# M_B_adapter_412.net
KiCad netlist of a schematic drawn in EAGLE
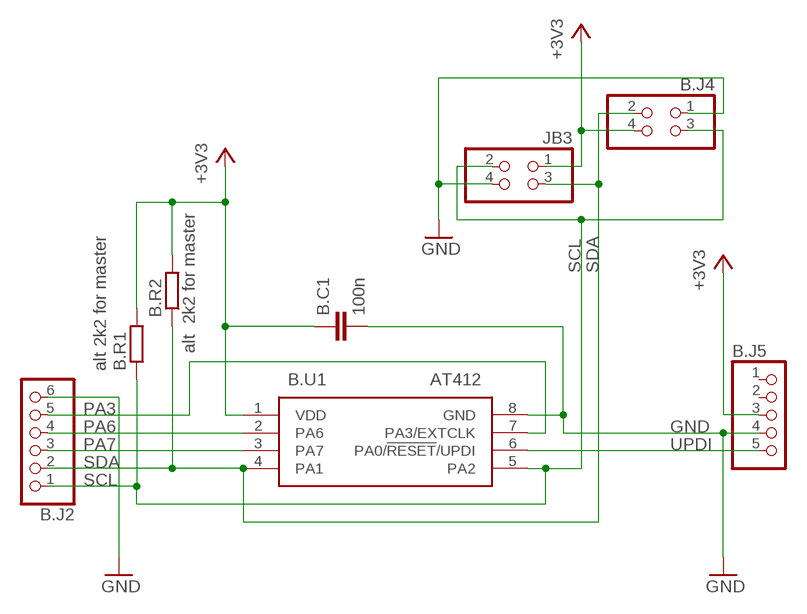
[diagram p0: schematic, sheet 1]

(export (version "E")
  (design (tool "Eeschema 10.0.6"))
  (components
    (comp (ref "B.C1")
      (value "100n")
      (footprint "eagle-import:C0603")
      (libsource (lib "eagle-import") (part "C-EUC0603"))
    )
    (comp (ref "B.J2")
      (value "PINHD-1X6")
      (footprint "eagle-import:1X06")
      (libsource (lib "eagle-import") (part "PINHD-1X6"))
    )
    (comp (ref "B.J4")
      (value "PINHD-2X2")
      (footprint "eagle-import:2X02")
      (libsource (lib "eagle-import") (part "PINHD-2X2"))
    )
    (comp (ref "B.J5")
      (value "PINHD-1X5")
      (footprint "eagle-import:1X05")
      (libsource (lib "eagle-import") (part "PINHD-1X5"))
    )
    (comp (ref "B.R1")
      (value "alt 2k2 for master")
      (footprint "eagle-import:R0603")
      (libsource (lib "eagle-import") (part "R-EU_R0603"))
    )
    (comp (ref "B.R2")
      (value "alt 2k2 for master")
      (footprint "eagle-import:R0603")
      (libsource (lib "eagle-import") (part "R-EU_R0603"))
    )
    (comp (ref "B.U1")
      (value "AT412")
      (footprint "eagle-import:SOIC127P600X175-8N")
      (fields
        (field (name "MANUFACTURER_PART_NUMBER") "ATTINY412-SSN")
        (field (name "MOUSER_PART_NUMBER") "579-ATTINY412-SSN")
      )
      (libsource (lib "eagle-import") (part "ATTINY412-SSN"))
    )
    (comp (ref "JB3")
      (value "PINHD-2X2")
      (footprint "eagle-import:2X02")
      (libsource (lib "eagle-import") (part "PINHD-2X2"))
    )
  )
  (nets
    (net (code "1") (name "+3V3") (class "Default")
      (node (ref "B.C1") (pin "1") (pinfunction "1_1") (pintype "passive"))
      (node (ref "B.J4") (pin "4") (pinfunction "4_4") (pintype "passive"))
      (node (ref "B.J5") (pin "3") (pinfunction "3_3") (pintype "passive"))
      (node (ref "B.R1") (pin "2") (pinfunction "2_2") (pintype "passive"))
      (node (ref "B.R2") (pin "2") (pinfunction "2_2") (pintype "passive"))
      (node (ref "B.U1") (pin "1") (pinfunction "VDD_1") (pintype "bidirectional"))
      (node (ref "JB3") (pin "1") (pinfunction "1_1") (pintype "passive"))
    )
    (net (code "2") (name "/PA3") (class "Default")
      (node (ref "B.J2") (pin "5") (pinfunction "5_5") (pintype "passive"))
      (node (ref "B.U1") (pin "7") (pinfunction "PA3/EXTCLK_7") (pintype "bidirectional"))
    )
    (net (code "3") (name "/PA6") (class "Default")
      (node (ref "B.J2") (pin "4") (pinfunction "4_4") (pintype "passive"))
      (node (ref "B.U1") (pin "2") (pinfunction "PA6_2") (pintype "bidirectional"))
    )
    (net (code "4") (name "/PA7") (class "Default")
      (node (ref "B.J2") (pin "3") (pinfunction "3_3") (pintype "passive"))
      (node (ref "B.U1") (pin "3") (pinfunction "PA7_3") (pintype "bidirectional"))
    )
    (net (code "5") (name "/SCL") (class "Default")
      (node (ref "B.J2") (pin "1") (pinfunction "1_1") (pintype "passive"))
      (node (ref "B.J4") (pin "3") (pinfunction "3_3") (pintype "passive"))
      (node (ref "B.R1") (pin "1") (pinfunction "1_1") (pintype "passive"))
      (node (ref "B.U1") (pin "5") (pinfunction "PA2_5") (pintype "bidirectional"))
      (node (ref "JB3") (pin "2") (pinfunction "2_2") (pintype "passive"))
    )
    (net (code "6") (name "/SDA") (class "Default")
      (node (ref "B.J2") (pin "2") (pinfunction "2_2") (pintype "passive"))
      (node (ref "B.J4") (pin "2") (pinfunction "2_2") (pintype "passive"))
      (node (ref "B.R2") (pin "1") (pinfunction "1_1") (pintype "passive"))
      (node (ref "B.U1") (pin "4") (pinfunction "PA1_4") (pintype "bidirectional"))
      (node (ref "JB3") (pin "3") (pinfunction "3_3") (pintype "passive"))
    )
    (net (code "7") (name "/UPDI") (class "Default")
      (node (ref "B.J5") (pin "5") (pinfunction "5_5") (pintype "passive"))
      (node (ref "B.U1") (pin "6") (pinfunction "PA0/~{RESET}/UPDI_6") (pintype "bidirectional"))
    )
    (net (code "8") (name "GND") (class "Default")
      (node (ref "B.C1") (pin "2") (pinfunction "2_2") (pintype "passive"))
      (node (ref "B.J2") (pin "6") (pinfunction "6_6") (pintype "passive"))
      (node (ref "B.J4") (pin "1") (pinfunction "1_1") (pintype "passive"))
      (node (ref "B.J5") (pin "4") (pinfunction "4_4") (pintype "passive"))
      (node (ref "B.U1") (pin "8") (pinfunction "GND_8") (pintype "bidirectional"))
      (node (ref "JB3") (pin "4") (pinfunction "4_4") (pintype "passive"))
    )
    (net (code "9") (name "unconnected-(B.J5-Pad1)") (class "Default")
      (node (ref "B.J5") (pin "1") (pinfunction "1_1") (pintype "passive"))
    )
    (net (code "10") (name "unconnected-(B.J5-Pad2)") (class "Default")
      (node (ref "B.J5") (pin "2") (pinfunction "2_2") (pintype "passive"))
    )
  )
)
